# BollardsAux.net
KiCad netlist of a schematic drawn in EAGLE
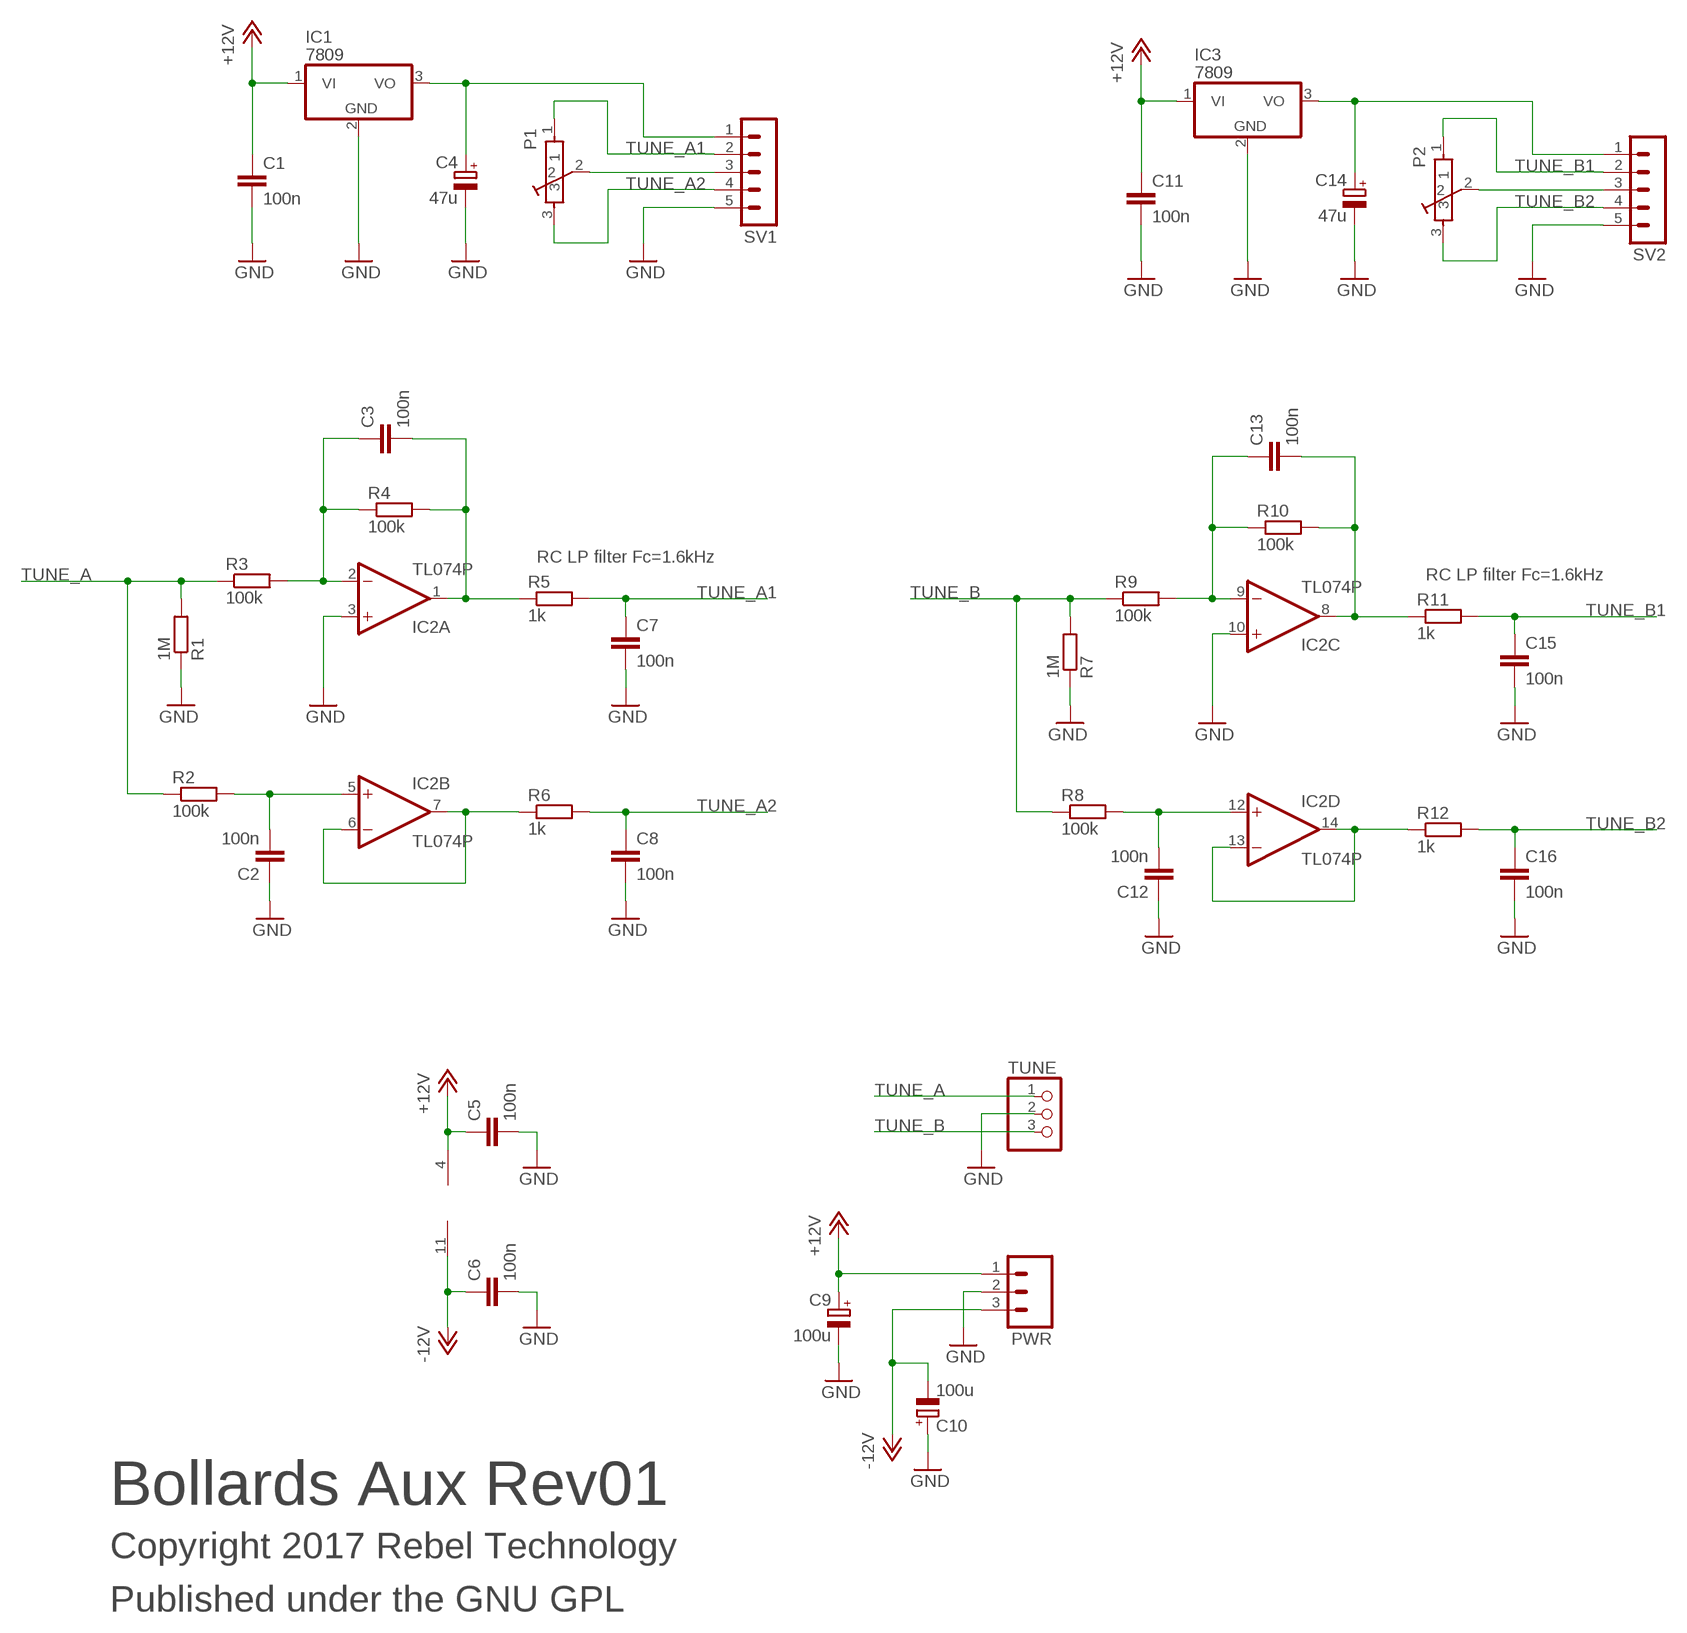
[diagram p0: schematic, sheet 1]

(export (version "E")
  (design (tool "Eeschema 10.0.6"))
  (components
    (comp (ref "C1")
      (value "100n")
      (footprint "eagle-import:C050-025X075")
      (libsource (lib "eagle-import") (part "C-EU050-025X075"))
    )
    (comp (ref "C2")
      (value "100n")
      (footprint "eagle-import:C050-025X075")
      (libsource (lib "eagle-import") (part "C-EU050-025X075"))
    )
    (comp (ref "C3")
      (value "100n")
      (footprint "eagle-import:C050-025X075")
      (libsource (lib "eagle-import") (part "C-EU050-025X075"))
    )
    (comp (ref "C4")
      (value "47u")
      (footprint "eagle-import:E2,5-7")
      (libsource (lib "eagle-import") (part "CPOL-EUE2.5-7"))
    )
    (comp (ref "C5")
      (value "100n")
      (footprint "eagle-import:C050-025X075")
      (libsource (lib "eagle-import") (part "C-EU050-025X075"))
    )
    (comp (ref "C6")
      (value "100n")
      (footprint "eagle-import:C050-025X075")
      (libsource (lib "eagle-import") (part "C-EU050-025X075"))
    )
    (comp (ref "C7")
      (value "100n")
      (footprint "eagle-import:C050-025X075")
      (libsource (lib "eagle-import") (part "C-EU050-025X075"))
    )
    (comp (ref "C8")
      (value "100n")
      (footprint "eagle-import:C050-025X075")
      (libsource (lib "eagle-import") (part "C-EU050-025X075"))
    )
    (comp (ref "C9")
      (value "100u")
      (footprint "eagle-import:E2,5-7")
      (libsource (lib "eagle-import") (part "CPOL-EUE2.5-7"))
    )
    (comp (ref "C10")
      (value "100u")
      (footprint "eagle-import:E2,5-7")
      (libsource (lib "eagle-import") (part "CPOL-EUE2.5-7"))
    )
    (comp (ref "C11")
      (value "100n")
      (footprint "eagle-import:C050-025X075")
      (libsource (lib "eagle-import") (part "C-EU050-025X075"))
    )
    (comp (ref "C12")
      (value "100n")
      (footprint "eagle-import:C050-025X075")
      (libsource (lib "eagle-import") (part "C-EU050-025X075"))
    )
    (comp (ref "C13")
      (value "100n")
      (footprint "eagle-import:C050-025X075")
      (libsource (lib "eagle-import") (part "C-EU050-025X075"))
    )
    (comp (ref "C14")
      (value "47u")
      (footprint "eagle-import:E2,5-7")
      (libsource (lib "eagle-import") (part "CPOL-EUE2.5-7"))
    )
    (comp (ref "C15")
      (value "100n")
      (footprint "eagle-import:C050-025X075")
      (libsource (lib "eagle-import") (part "C-EU050-025X075"))
    )
    (comp (ref "C16")
      (value "100n")
      (footprint "eagle-import:C050-025X075")
      (libsource (lib "eagle-import") (part "C-EU050-025X075"))
    )
    (comp (ref "IC1")
      (value "7809")
      (footprint "eagle-import:TO220H")
      (libsource (lib "eagle-import") (part "78T05"))
    )
    (comp (ref "IC2")
      (value "TL074P")
      (footprint "eagle-import:DIL14")
      (libsource (lib "eagle-import") (part "TL074P"))
    )
    (comp (ref "IC3")
      (value "7809")
      (footprint "eagle-import:TO220H")
      (libsource (lib "eagle-import") (part "78T05"))
    )
    (comp (ref "P1")
      (value "100k")
      (footprint "eagle-import:POT-BOURNS-PTD901")
      (libsource (lib "eagle-import") (part "POT-BOURNS-PTD901"))
    )
    (comp (ref "P2")
      (value "100k")
      (footprint "eagle-import:POT-BOURNS-PTD901")
      (libsource (lib "eagle-import") (part "POT-BOURNS-PTD901"))
    )
    (comp (ref "PWR")
      (value "M03PTH")
      (footprint "eagle-import:1X03")
      (libsource (lib "eagle-import") (part "M03PTH"))
    )
    (comp (ref "R1")
      (value "1M")
      (footprint "eagle-import:0204_7")
      (libsource (lib "eagle-import") (part "R-EU_0204/7"))
    )
    (comp (ref "R2")
      (value "100k")
      (footprint "eagle-import:0204_7")
      (libsource (lib "eagle-import") (part "R-EU_0204/7"))
    )
    (comp (ref "R3")
      (value "100k")
      (footprint "eagle-import:0204_7")
      (libsource (lib "eagle-import") (part "R-EU_0204/7"))
    )
    (comp (ref "R4")
      (value "100k")
      (footprint "eagle-import:0204_7")
      (libsource (lib "eagle-import") (part "R-EU_0204/7"))
    )
    (comp (ref "R5")
      (value "1k")
      (footprint "eagle-import:0204_7")
      (libsource (lib "eagle-import") (part "R-EU_0204/7"))
    )
    (comp (ref "R6")
      (value "1k")
      (footprint "eagle-import:0204_7")
      (libsource (lib "eagle-import") (part "R-EU_0204/7"))
    )
    (comp (ref "R7")
      (value "1M")
      (footprint "eagle-import:0204_7")
      (libsource (lib "eagle-import") (part "R-EU_0204/7"))
    )
    (comp (ref "R8")
      (value "100k")
      (footprint "eagle-import:0204_7")
      (libsource (lib "eagle-import") (part "R-EU_0204/7"))
    )
    (comp (ref "R9")
      (value "100k")
      (footprint "eagle-import:0204_7")
      (libsource (lib "eagle-import") (part "R-EU_0204/7"))
    )
    (comp (ref "R10")
      (value "100k")
      (footprint "eagle-import:0204_7")
      (libsource (lib "eagle-import") (part "R-EU_0204/7"))
    )
    (comp (ref "R11")
      (value "1k")
      (footprint "eagle-import:0204_7")
      (libsource (lib "eagle-import") (part "R-EU_0204/7"))
    )
    (comp (ref "R12")
      (value "1k")
      (footprint "eagle-import:0204_7")
      (libsource (lib "eagle-import") (part "R-EU_0204/7"))
    )
    (comp (ref "SV1")
      (value "MA05-1")
      (footprint "eagle-import:MA05-1")
      (libsource (lib "eagle-import") (part "MA05-1"))
    )
    (comp (ref "SV2")
      (value "MA05-1")
      (footprint "eagle-import:MA05-1")
      (libsource (lib "eagle-import") (part "MA05-1"))
    )
    (comp (ref "TUNE")
      (value "CON-JST-1X03PH-TH")
      (footprint "eagle-import:JST-B3B-PH-KL")
      (libsource (lib "eagle-import") (part "CON-JST-1X03PH-TH"))
    )
  )
  (nets
    (net (code "1") (name "+12V") (class "Default")
      (node (ref "C1") (pin "1") (pinfunction "1_1") (pintype "passive"))
      (node (ref "C11") (pin "1") (pinfunction "1_1") (pintype "passive"))
      (node (ref "C5") (pin "1") (pinfunction "1_1") (pintype "passive"))
      (node (ref "C9") (pin "+") (pinfunction "+_+") (pintype "passive"))
      (node (ref "IC1") (pin "1") (pinfunction "VI_1") (pintype "input"))
      (node (ref "IC2") (pin "4") (pinfunction "V+_4") (pintype "power_in"))
      (node (ref "IC3") (pin "1") (pinfunction "VI_1") (pintype "input"))
      (node (ref "PWR") (pin "1") (pinfunction "1_1") (pintype "passive"))
    )
    (net (code "2") (name "-12V") (class "Default")
      (node (ref "C10") (pin "-") (pinfunction "-_-") (pintype "passive"))
      (node (ref "C6") (pin "1") (pinfunction "1_1") (pintype "passive"))
      (node (ref "IC2") (pin "11") (pinfunction "V-_11") (pintype "power_in"))
      (node (ref "PWR") (pin "3") (pinfunction "3_3") (pintype "passive"))
    )
    (net (code "3") (name "/TUNE_A") (class "Default")
      (node (ref "R1") (pin "2") (pinfunction "2_2") (pintype "passive"))
      (node (ref "R2") (pin "1") (pinfunction "1_1") (pintype "passive"))
      (node (ref "R3") (pin "1") (pinfunction "1_1") (pintype "passive"))
      (node (ref "TUNE") (pin "1") (pinfunction "1_1") (pintype "passive"))
    )
    (net (code "4") (name "/TUNE_A1") (class "Default")
      (node (ref "C7") (pin "1") (pinfunction "1_1") (pintype "passive"))
      (node (ref "P1") (pin "1") (pinfunction "1_1") (pintype "bidirectional"))
      (node (ref "R5") (pin "2") (pinfunction "2_2") (pintype "passive"))
      (node (ref "SV1") (pin "2") (pinfunction "2_2") (pintype "passive"))
    )
    (net (code "5") (name "/TUNE_A2") (class "Default")
      (node (ref "C8") (pin "1") (pinfunction "1_1") (pintype "passive"))
      (node (ref "P1") (pin "3") (pinfunction "3_3") (pintype "bidirectional"))
      (node (ref "R6") (pin "2") (pinfunction "2_2") (pintype "passive"))
      (node (ref "SV1") (pin "4") (pinfunction "4_4") (pintype "passive"))
    )
    (net (code "6") (name "/TUNE_B") (class "Default")
      (node (ref "R7") (pin "2") (pinfunction "2_2") (pintype "passive"))
      (node (ref "R8") (pin "1") (pinfunction "1_1") (pintype "passive"))
      (node (ref "R9") (pin "1") (pinfunction "1_1") (pintype "passive"))
      (node (ref "TUNE") (pin "3") (pinfunction "3_3") (pintype "passive"))
    )
    (net (code "7") (name "/TUNE_B1") (class "Default")
      (node (ref "C15") (pin "1") (pinfunction "1_1") (pintype "passive"))
      (node (ref "P2") (pin "1") (pinfunction "1_1") (pintype "bidirectional"))
      (node (ref "R11") (pin "2") (pinfunction "2_2") (pintype "passive"))
      (node (ref "SV2") (pin "2") (pinfunction "2_2") (pintype "passive"))
    )
    (net (code "8") (name "/TUNE_B2") (class "Default")
      (node (ref "C16") (pin "1") (pinfunction "1_1") (pintype "passive"))
      (node (ref "P2") (pin "3") (pinfunction "3_3") (pintype "bidirectional"))
      (node (ref "R12") (pin "2") (pinfunction "2_2") (pintype "passive"))
      (node (ref "SV2") (pin "4") (pinfunction "4_4") (pintype "passive"))
    )
    (net (code "9") (name "GND") (class "Default")
      (node (ref "C1") (pin "2") (pinfunction "2_2") (pintype "passive"))
      (node (ref "C10") (pin "+") (pinfunction "+_+") (pintype "passive"))
      (node (ref "C11") (pin "2") (pinfunction "2_2") (pintype "passive"))
      (node (ref "C12") (pin "1") (pinfunction "1_1") (pintype "passive"))
      (node (ref "C14") (pin "-") (pinfunction "-_-") (pintype "passive"))
      (node (ref "C15") (pin "2") (pinfunction "2_2") (pintype "passive"))
      (node (ref "C16") (pin "2") (pinfunction "2_2") (pintype "passive"))
      (node (ref "C2") (pin "1") (pinfunction "1_1") (pintype "passive"))
      (node (ref "C4") (pin "-") (pinfunction "-_-") (pintype "passive"))
      (node (ref "C5") (pin "2") (pinfunction "2_2") (pintype "passive"))
      (node (ref "C6") (pin "2") (pinfunction "2_2") (pintype "passive"))
      (node (ref "C7") (pin "2") (pinfunction "2_2") (pintype "passive"))
      (node (ref "C8") (pin "2") (pinfunction "2_2") (pintype "passive"))
      (node (ref "C9") (pin "-") (pinfunction "-_-") (pintype "passive"))
      (node (ref "IC1") (pin "2") (pinfunction "GND_2") (pintype "passive"))
      (node (ref "IC2") (pin "10") (pinfunction "+IN_10") (pintype "input"))
      (node (ref "IC2") (pin "3") (pinfunction "+IN_3") (pintype "input"))
      (node (ref "IC3") (pin "2") (pinfunction "GND_2") (pintype "passive"))
      (node (ref "PWR") (pin "2") (pinfunction "2_2") (pintype "passive"))
      (node (ref "R1") (pin "1") (pinfunction "1_1") (pintype "passive"))
      (node (ref "R7") (pin "1") (pinfunction "1_1") (pintype "passive"))
      (node (ref "SV1") (pin "5") (pinfunction "5_5") (pintype "passive"))
      (node (ref "SV2") (pin "5") (pinfunction "5_5") (pintype "passive"))
      (node (ref "TUNE") (pin "2") (pinfunction "2_2") (pintype "passive"))
    )
    (net (code "10") (name "Net-(IC1-VO)") (class "Default")
      (node (ref "C4") (pin "+") (pinfunction "+_+") (pintype "passive"))
      (node (ref "IC1") (pin "3") (pinfunction "VO_3") (pintype "passive"))
      (node (ref "SV1") (pin "1") (pinfunction "1_1") (pintype "passive"))
    )
    (net (code "11") (name "Net-(IC2A--IN)") (class "Default")
      (node (ref "C3") (pin "1") (pinfunction "1_1") (pintype "passive"))
      (node (ref "IC2") (pin "2") (pinfunction "-IN_2") (pintype "input"))
      (node (ref "R3") (pin "2") (pinfunction "2_2") (pintype "passive"))
      (node (ref "R4") (pin "1") (pinfunction "1_1") (pintype "passive"))
    )
    (net (code "12") (name "Net-(IC2A-OUT)") (class "Default")
      (node (ref "C3") (pin "2") (pinfunction "2_2") (pintype "passive"))
      (node (ref "IC2") (pin "1") (pinfunction "OUT_1") (pintype "output"))
      (node (ref "R4") (pin "2") (pinfunction "2_2") (pintype "passive"))
      (node (ref "R5") (pin "1") (pinfunction "1_1") (pintype "passive"))
    )
    (net (code "13") (name "Net-(IC2B-+IN)") (class "Default")
      (node (ref "C2") (pin "2") (pinfunction "2_2") (pintype "passive"))
      (node (ref "IC2") (pin "5") (pinfunction "+IN_5") (pintype "input"))
      (node (ref "R2") (pin "2") (pinfunction "2_2") (pintype "passive"))
    )
    (net (code "14") (name "Net-(IC2B--IN)") (class "Default")
      (node (ref "IC2") (pin "6") (pinfunction "-IN_6") (pintype "input"))
      (node (ref "IC2") (pin "7") (pinfunction "OUT_7") (pintype "output"))
      (node (ref "R6") (pin "1") (pinfunction "1_1") (pintype "passive"))
    )
    (net (code "15") (name "Net-(IC2C--IN)") (class "Default")
      (node (ref "C13") (pin "1") (pinfunction "1_1") (pintype "passive"))
      (node (ref "IC2") (pin "9") (pinfunction "-IN_9") (pintype "input"))
      (node (ref "R10") (pin "1") (pinfunction "1_1") (pintype "passive"))
      (node (ref "R9") (pin "2") (pinfunction "2_2") (pintype "passive"))
    )
    (net (code "16") (name "Net-(IC2C-OUT)") (class "Default")
      (node (ref "C13") (pin "2") (pinfunction "2_2") (pintype "passive"))
      (node (ref "IC2") (pin "8") (pinfunction "OUT_8") (pintype "output"))
      (node (ref "R10") (pin "2") (pinfunction "2_2") (pintype "passive"))
      (node (ref "R11") (pin "1") (pinfunction "1_1") (pintype "passive"))
    )
    (net (code "17") (name "Net-(IC2D-+IN)") (class "Default")
      (node (ref "C12") (pin "2") (pinfunction "2_2") (pintype "passive"))
      (node (ref "IC2") (pin "12") (pinfunction "+IN_12") (pintype "input"))
      (node (ref "R8") (pin "2") (pinfunction "2_2") (pintype "passive"))
    )
    (net (code "18") (name "Net-(IC2D--IN)") (class "Default")
      (node (ref "IC2") (pin "13") (pinfunction "-IN_13") (pintype "input"))
      (node (ref "IC2") (pin "14") (pinfunction "OUT_14") (pintype "output"))
      (node (ref "R12") (pin "1") (pinfunction "1_1") (pintype "passive"))
    )
    (net (code "19") (name "Net-(IC3-VO)") (class "Default")
      (node (ref "C14") (pin "+") (pinfunction "+_+") (pintype "passive"))
      (node (ref "IC3") (pin "3") (pinfunction "VO_3") (pintype "passive"))
      (node (ref "SV2") (pin "1") (pinfunction "1_1") (pintype "passive"))
    )
    (net (code "20") (name "Net-(P1-Pad2)") (class "Default")
      (node (ref "P1") (pin "2") (pinfunction "2_2") (pintype "bidirectional"))
      (node (ref "SV1") (pin "3") (pinfunction "3_3") (pintype "passive"))
    )
    (net (code "21") (name "Net-(P2-Pad2)") (class "Default")
      (node (ref "P2") (pin "2") (pinfunction "2_2") (pintype "bidirectional"))
      (node (ref "SV2") (pin "3") (pinfunction "3_3") (pintype "passive"))
    )
  )
)
